# low-voltage-detector.net
KiCad netlist of a schematic drawn in EAGLE
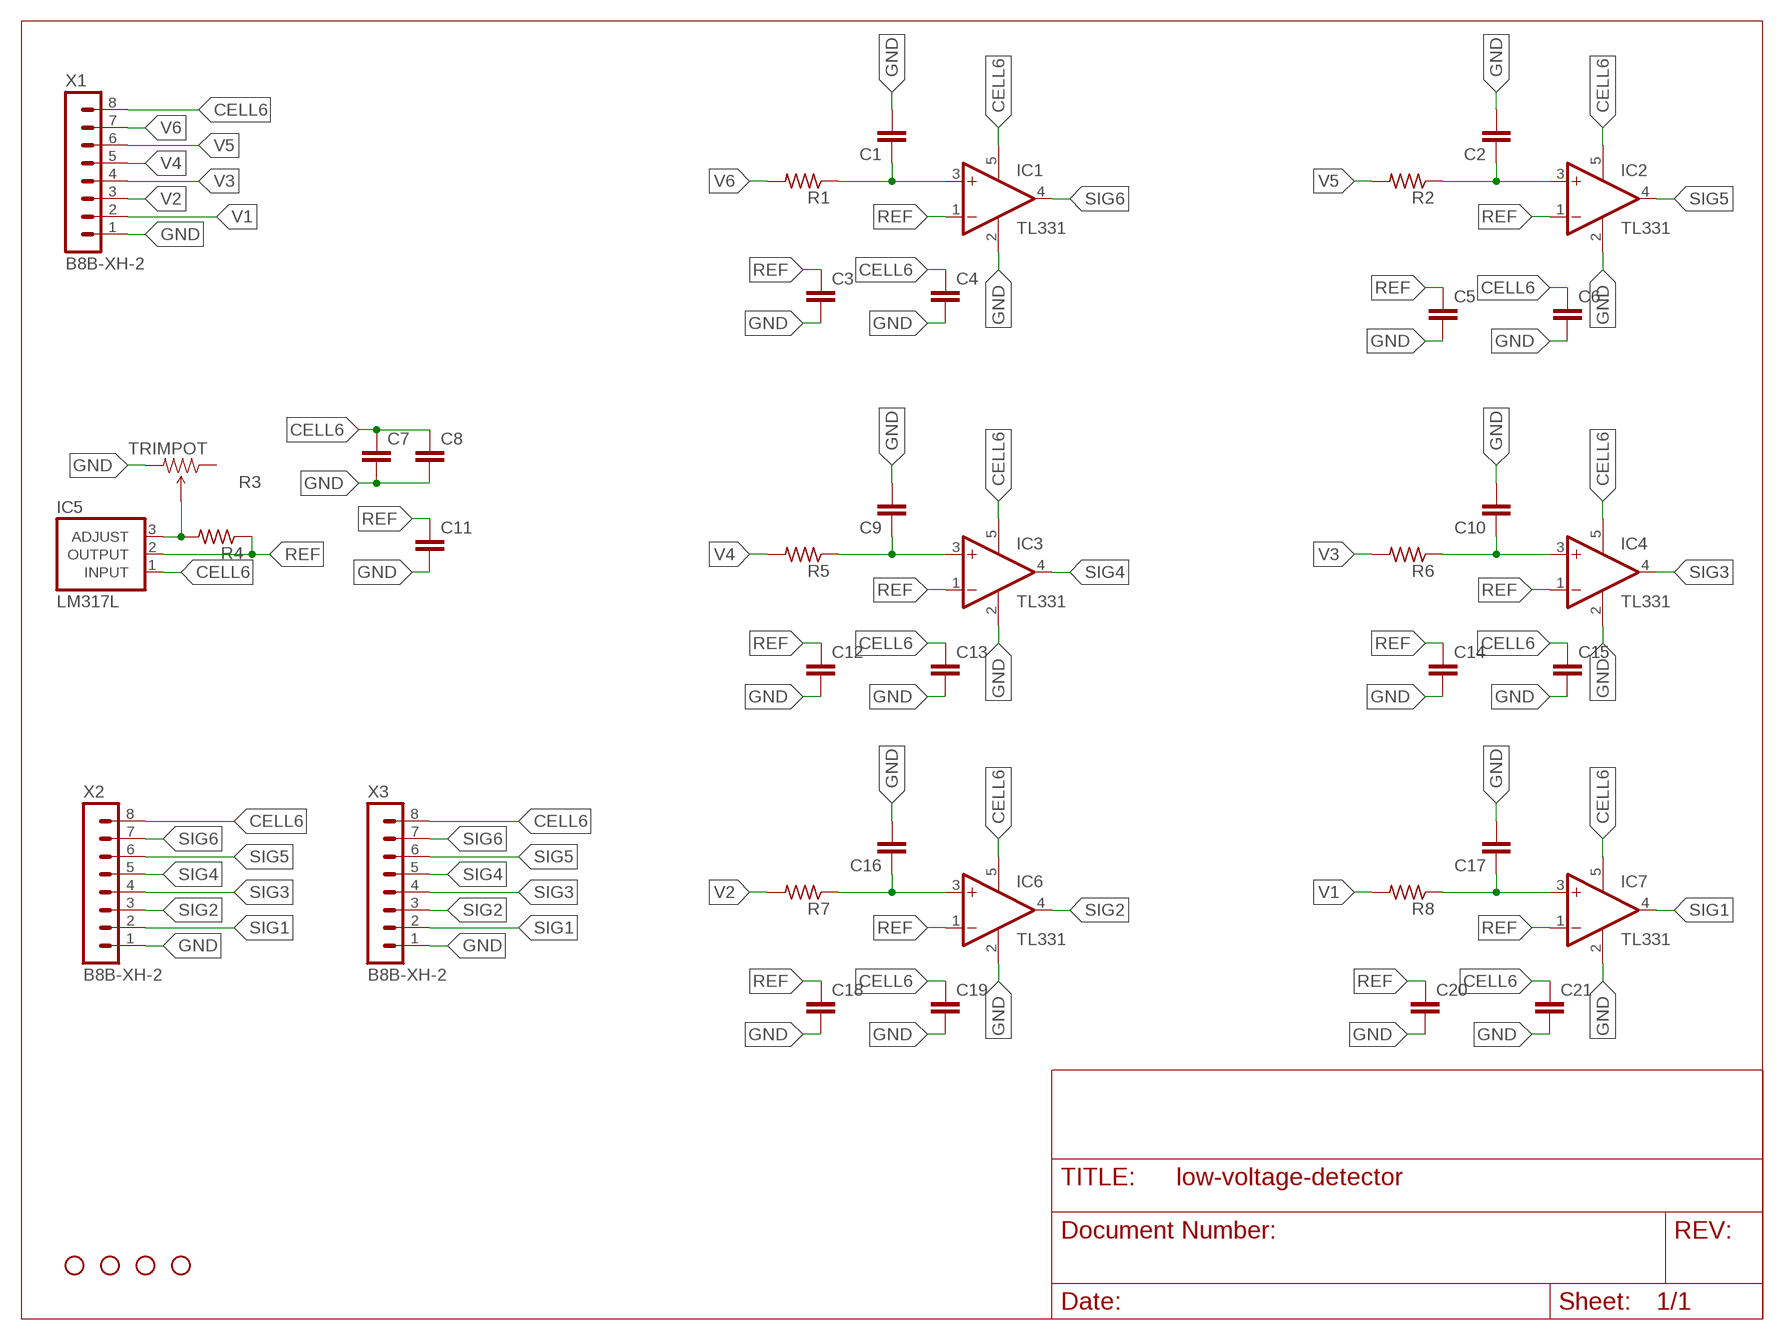
[diagram p0: schematic, sheet 1]

(export (version "E")
  (design (tool "Eeschema 10.0.6"))
  (components
    (comp (ref "C1")
      (value "CAPACITOR_0805")
      (footprint "eagle-import:0805")
      (libsource (lib "eagle-import") (part "CAPACITOR_0805"))
    )
    (comp (ref "C2")
      (value "CAPACITOR_0805")
      (footprint "eagle-import:0805")
      (libsource (lib "eagle-import") (part "CAPACITOR_0805"))
    )
    (comp (ref "C3")
      (value "CAPACITOR_0805")
      (footprint "eagle-import:0805")
      (libsource (lib "eagle-import") (part "CAPACITOR_0805"))
    )
    (comp (ref "C4")
      (value "CAPACITOR_0805")
      (footprint "eagle-import:0805")
      (libsource (lib "eagle-import") (part "CAPACITOR_0805"))
    )
    (comp (ref "C5")
      (value "CAPACITOR_0805")
      (footprint "eagle-import:0805")
      (libsource (lib "eagle-import") (part "CAPACITOR_0805"))
    )
    (comp (ref "C6")
      (value "CAPACITOR_0805")
      (footprint "eagle-import:0805")
      (libsource (lib "eagle-import") (part "CAPACITOR_0805"))
    )
    (comp (ref "C7")
      (value "CAPACITOR_0805")
      (footprint "eagle-import:0805")
      (libsource (lib "eagle-import") (part "CAPACITOR_0805"))
    )
    (comp (ref "C8")
      (value "CAPACITOR_0805")
      (footprint "eagle-import:0805")
      (libsource (lib "eagle-import") (part "CAPACITOR_0805"))
    )
    (comp (ref "C9")
      (value "CAPACITOR_0805")
      (footprint "eagle-import:0805")
      (libsource (lib "eagle-import") (part "CAPACITOR_0805"))
    )
    (comp (ref "C10")
      (value "CAPACITOR_0805")
      (footprint "eagle-import:0805")
      (libsource (lib "eagle-import") (part "CAPACITOR_0805"))
    )
    (comp (ref "C11")
      (value "CAPACITOR_0805")
      (footprint "eagle-import:0805")
      (libsource (lib "eagle-import") (part "CAPACITOR_0805"))
    )
    (comp (ref "C12")
      (value "CAPACITOR_0805")
      (footprint "eagle-import:0805")
      (libsource (lib "eagle-import") (part "CAPACITOR_0805"))
    )
    (comp (ref "C13")
      (value "CAPACITOR_0805")
      (footprint "eagle-import:0805")
      (libsource (lib "eagle-import") (part "CAPACITOR_0805"))
    )
    (comp (ref "C14")
      (value "CAPACITOR_0805")
      (footprint "eagle-import:0805")
      (libsource (lib "eagle-import") (part "CAPACITOR_0805"))
    )
    (comp (ref "C15")
      (value "CAPACITOR_0805")
      (footprint "eagle-import:0805")
      (libsource (lib "eagle-import") (part "CAPACITOR_0805"))
    )
    (comp (ref "C16")
      (value "CAPACITOR_0805")
      (footprint "eagle-import:0805")
      (libsource (lib "eagle-import") (part "CAPACITOR_0805"))
    )
    (comp (ref "C17")
      (value "CAPACITOR_0805")
      (footprint "eagle-import:0805")
      (libsource (lib "eagle-import") (part "CAPACITOR_0805"))
    )
    (comp (ref "C18")
      (value "CAPACITOR_0805")
      (footprint "eagle-import:0805")
      (libsource (lib "eagle-import") (part "CAPACITOR_0805"))
    )
    (comp (ref "C19")
      (value "CAPACITOR_0805")
      (footprint "eagle-import:0805")
      (libsource (lib "eagle-import") (part "CAPACITOR_0805"))
    )
    (comp (ref "C20")
      (value "CAPACITOR_0805")
      (footprint "eagle-import:0805")
      (libsource (lib "eagle-import") (part "CAPACITOR_0805"))
    )
    (comp (ref "C21")
      (value "CAPACITOR_0805")
      (footprint "eagle-import:0805")
      (libsource (lib "eagle-import") (part "CAPACITOR_0805"))
    )
    (comp (ref "H1")
      (value "STAND-OFF")
      (footprint "eagle-import:STAND-OFF")
      (libsource (lib "eagle-import") (part "STAND-OFF"))
    )
    (comp (ref "H2")
      (value "STAND-OFF")
      (footprint "eagle-import:STAND-OFF")
      (libsource (lib "eagle-import") (part "STAND-OFF"))
    )
    (comp (ref "H3")
      (value "STAND-OFF")
      (footprint "eagle-import:STAND-OFF")
      (libsource (lib "eagle-import") (part "STAND-OFF"))
    )
    (comp (ref "H4")
      (value "STAND-OFF")
      (footprint "eagle-import:STAND-OFF")
      (libsource (lib "eagle-import") (part "STAND-OFF"))
    )
    (comp (ref "IC1")
      (value "TL331")
      (footprint "eagle-import:DBV-R-PDSO-G5")
      (libsource (lib "eagle-import") (part "TL331"))
    )
    (comp (ref "IC2")
      (value "TL331")
      (footprint "eagle-import:DBV-R-PDSO-G5")
      (libsource (lib "eagle-import") (part "TL331"))
    )
    (comp (ref "IC3")
      (value "TL331")
      (footprint "eagle-import:DBV-R-PDSO-G5")
      (libsource (lib "eagle-import") (part "TL331"))
    )
    (comp (ref "IC4")
      (value "TL331")
      (footprint "eagle-import:DBV-R-PDSO-G5")
      (libsource (lib "eagle-import") (part "TL331"))
    )
    (comp (ref "IC5")
      (value "LM317L")
      (footprint "eagle-import:TO92")
      (libsource (lib "eagle-import") (part "LINEAR-REGULATOR_LM317L"))
    )
    (comp (ref "IC6")
      (value "TL331")
      (footprint "eagle-import:DBV-R-PDSO-G5")
      (libsource (lib "eagle-import") (part "TL331"))
    )
    (comp (ref "IC7")
      (value "TL331")
      (footprint "eagle-import:DBV-R-PDSO-G5")
      (libsource (lib "eagle-import") (part "TL331"))
    )
    (comp (ref "R1")
      (value "R-US_R0805")
      (footprint "eagle-import:R0805")
      (libsource (lib "eagle-import") (part "R-US_R0805"))
    )
    (comp (ref "R2")
      (value "R-US_R0805")
      (footprint "eagle-import:R0805")
      (libsource (lib "eagle-import") (part "R-US_R0805"))
    )
    (comp (ref "R3")
      (value "TRIMPOT")
      (footprint "eagle-import:490-2877-ND")
      (libsource (lib "eagle-import") (part "TRIMPOT"))
    )
    (comp (ref "R4")
      (value "R-US_R0805")
      (footprint "eagle-import:R0805")
      (libsource (lib "eagle-import") (part "R-US_R0805"))
    )
    (comp (ref "R5")
      (value "R-US_R0805")
      (footprint "eagle-import:R0805")
      (libsource (lib "eagle-import") (part "R-US_R0805"))
    )
    (comp (ref "R6")
      (value "R-US_R0805")
      (footprint "eagle-import:R0805")
      (libsource (lib "eagle-import") (part "R-US_R0805"))
    )
    (comp (ref "R7")
      (value "R-US_R0805")
      (footprint "eagle-import:R0805")
      (libsource (lib "eagle-import") (part "R-US_R0805"))
    )
    (comp (ref "R8")
      (value "R-US_R0805")
      (footprint "eagle-import:R0805")
      (libsource (lib "eagle-import") (part "R-US_R0805"))
    )
    (comp (ref "X1")
      (value "B8B-XH-2")
      (footprint "eagle-import:B8B-XH-A")
      (libsource (lib "eagle-import") (part "B8B-XH-2"))
    )
    (comp (ref "X2")
      (value "B8B-XH-2")
      (footprint "eagle-import:B8B-XH-A")
      (libsource (lib "eagle-import") (part "B8B-XH-2"))
    )
    (comp (ref "X3")
      (value "B8B-XH-2")
      (footprint "eagle-import:B8B-XH-A")
      (libsource (lib "eagle-import") (part "B8B-XH-2"))
    )
  )
  (nets
    (net (code "1") (name "CELL6") (class "Default")
      (node (ref "C13") (pin "1") (pinfunction "1_1") (pintype "passive"))
      (node (ref "C15") (pin "1") (pinfunction "1_1") (pintype "passive"))
      (node (ref "C19") (pin "1") (pinfunction "1_1") (pintype "passive"))
      (node (ref "C21") (pin "1") (pinfunction "1_1") (pintype "passive"))
      (node (ref "C4") (pin "1") (pinfunction "1_1") (pintype "passive"))
      (node (ref "C6") (pin "1") (pinfunction "1_1") (pintype "passive"))
      (node (ref "C7") (pin "1") (pinfunction "1_1") (pintype "passive"))
      (node (ref "C8") (pin "1") (pinfunction "1_1") (pintype "passive"))
      (node (ref "IC1") (pin "5") (pinfunction "V+_5") (pintype "power_in"))
      (node (ref "IC2") (pin "5") (pinfunction "V+_5") (pintype "power_in"))
      (node (ref "IC3") (pin "5") (pinfunction "V+_5") (pintype "power_in"))
      (node (ref "IC4") (pin "5") (pinfunction "V+_5") (pintype "power_in"))
      (node (ref "IC5") (pin "1") (pinfunction "INPUT_1") (pintype "bidirectional"))
      (node (ref "IC6") (pin "5") (pinfunction "V+_5") (pintype "power_in"))
      (node (ref "IC7") (pin "5") (pinfunction "V+_5") (pintype "power_in"))
      (node (ref "X1") (pin "8") (pinfunction "8_8") (pintype "passive"))
      (node (ref "X2") (pin "8") (pinfunction "8_8") (pintype "passive"))
      (node (ref "X3") (pin "8") (pinfunction "8_8") (pintype "passive"))
    )
    (net (code "2") (name "GND") (class "Default")
      (node (ref "C1") (pin "2") (pinfunction "2_2") (pintype "passive"))
      (node (ref "C10") (pin "2") (pinfunction "2_2") (pintype "passive"))
      (node (ref "C11") (pin "2") (pinfunction "2_2") (pintype "passive"))
      (node (ref "C12") (pin "2") (pinfunction "2_2") (pintype "passive"))
      (node (ref "C13") (pin "2") (pinfunction "2_2") (pintype "passive"))
      (node (ref "C14") (pin "2") (pinfunction "2_2") (pintype "passive"))
      (node (ref "C15") (pin "2") (pinfunction "2_2") (pintype "passive"))
      (node (ref "C16") (pin "2") (pinfunction "2_2") (pintype "passive"))
      (node (ref "C17") (pin "2") (pinfunction "2_2") (pintype "passive"))
      (node (ref "C18") (pin "2") (pinfunction "2_2") (pintype "passive"))
      (node (ref "C19") (pin "2") (pinfunction "2_2") (pintype "passive"))
      (node (ref "C2") (pin "2") (pinfunction "2_2") (pintype "passive"))
      (node (ref "C20") (pin "2") (pinfunction "2_2") (pintype "passive"))
      (node (ref "C21") (pin "2") (pinfunction "2_2") (pintype "passive"))
      (node (ref "C3") (pin "2") (pinfunction "2_2") (pintype "passive"))
      (node (ref "C4") (pin "2") (pinfunction "2_2") (pintype "passive"))
      (node (ref "C5") (pin "2") (pinfunction "2_2") (pintype "passive"))
      (node (ref "C6") (pin "2") (pinfunction "2_2") (pintype "passive"))
      (node (ref "C7") (pin "2") (pinfunction "2_2") (pintype "passive"))
      (node (ref "C8") (pin "2") (pinfunction "2_2") (pintype "passive"))
      (node (ref "C9") (pin "2") (pinfunction "2_2") (pintype "passive"))
      (node (ref "IC1") (pin "2") (pinfunction "GND_2") (pintype "power_in"))
      (node (ref "IC2") (pin "2") (pinfunction "GND_2") (pintype "power_in"))
      (node (ref "IC3") (pin "2") (pinfunction "GND_2") (pintype "power_in"))
      (node (ref "IC4") (pin "2") (pinfunction "GND_2") (pintype "power_in"))
      (node (ref "IC6") (pin "2") (pinfunction "GND_2") (pintype "power_in"))
      (node (ref "IC7") (pin "2") (pinfunction "GND_2") (pintype "power_in"))
      (node (ref "R3") (pin "P$3") (pinfunction "CW_P$3") (pintype "passive"))
      (node (ref "X1") (pin "1") (pinfunction "1_1") (pintype "passive"))
      (node (ref "X2") (pin "1") (pinfunction "1_1") (pintype "passive"))
      (node (ref "X3") (pin "1") (pinfunction "1_1") (pintype "passive"))
    )
    (net (code "3") (name "Net-(IC1-+IN)") (class "Default")
      (node (ref "C1") (pin "1") (pinfunction "1_1") (pintype "passive"))
      (node (ref "IC1") (pin "3") (pinfunction "+IN_3") (pintype "input"))
      (node (ref "R1") (pin "1") (pinfunction "1_1") (pintype "passive"))
    )
    (net (code "4") (name "Net-(IC2-+IN)") (class "Default")
      (node (ref "C2") (pin "1") (pinfunction "1_1") (pintype "passive"))
      (node (ref "IC2") (pin "3") (pinfunction "+IN_3") (pintype "input"))
      (node (ref "R2") (pin "1") (pinfunction "1_1") (pintype "passive"))
    )
    (net (code "5") (name "Net-(IC3-+IN)") (class "Default")
      (node (ref "C9") (pin "1") (pinfunction "1_1") (pintype "passive"))
      (node (ref "IC3") (pin "3") (pinfunction "+IN_3") (pintype "input"))
      (node (ref "R5") (pin "1") (pinfunction "1_1") (pintype "passive"))
    )
    (net (code "6") (name "Net-(IC4-+IN)") (class "Default")
      (node (ref "C10") (pin "1") (pinfunction "1_1") (pintype "passive"))
      (node (ref "IC4") (pin "3") (pinfunction "+IN_3") (pintype "input"))
      (node (ref "R6") (pin "1") (pinfunction "1_1") (pintype "passive"))
    )
    (net (code "7") (name "Net-(IC5-ADJUST)") (class "Default")
      (node (ref "IC5") (pin "3") (pinfunction "ADJUST_3") (pintype "bidirectional"))
      (node (ref "R3") (pin "P$2") (pinfunction "WIPER_P$2") (pintype "passive"))
      (node (ref "R4") (pin "2") (pinfunction "2_2") (pintype "passive"))
    )
    (net (code "8") (name "Net-(IC6-+IN)") (class "Default")
      (node (ref "C16") (pin "1") (pinfunction "1_1") (pintype "passive"))
      (node (ref "IC6") (pin "3") (pinfunction "+IN_3") (pintype "input"))
      (node (ref "R7") (pin "1") (pinfunction "1_1") (pintype "passive"))
    )
    (net (code "9") (name "Net-(IC7-+IN)") (class "Default")
      (node (ref "C17") (pin "1") (pinfunction "1_1") (pintype "passive"))
      (node (ref "IC7") (pin "3") (pinfunction "+IN_3") (pintype "input"))
      (node (ref "R8") (pin "1") (pinfunction "1_1") (pintype "passive"))
    )
    (net (code "10") (name "REF") (class "Default")
      (node (ref "C11") (pin "1") (pinfunction "1_1") (pintype "passive"))
      (node (ref "C12") (pin "1") (pinfunction "1_1") (pintype "passive"))
      (node (ref "C14") (pin "1") (pinfunction "1_1") (pintype "passive"))
      (node (ref "C18") (pin "1") (pinfunction "1_1") (pintype "passive"))
      (node (ref "C20") (pin "1") (pinfunction "1_1") (pintype "passive"))
      (node (ref "C3") (pin "1") (pinfunction "1_1") (pintype "passive"))
      (node (ref "C5") (pin "1") (pinfunction "1_1") (pintype "passive"))
      (node (ref "IC1") (pin "1") (pinfunction "-IN_1") (pintype "input"))
      (node (ref "IC2") (pin "1") (pinfunction "-IN_1") (pintype "input"))
      (node (ref "IC3") (pin "1") (pinfunction "-IN_1") (pintype "input"))
      (node (ref "IC4") (pin "1") (pinfunction "-IN_1") (pintype "input"))
      (node (ref "IC5") (pin "2") (pinfunction "OUTPUT_2") (pintype "bidirectional"))
      (node (ref "IC6") (pin "1") (pinfunction "-IN_1") (pintype "input"))
      (node (ref "IC7") (pin "1") (pinfunction "-IN_1") (pintype "input"))
      (node (ref "R4") (pin "1") (pinfunction "1_1") (pintype "passive"))
    )
    (net (code "11") (name "SIG1") (class "Default")
      (node (ref "IC7") (pin "4") (pinfunction "OUT_4") (pintype "output"))
      (node (ref "X2") (pin "2") (pinfunction "2_2") (pintype "passive"))
      (node (ref "X3") (pin "2") (pinfunction "2_2") (pintype "passive"))
    )
    (net (code "12") (name "SIG2") (class "Default")
      (node (ref "IC6") (pin "4") (pinfunction "OUT_4") (pintype "output"))
      (node (ref "X2") (pin "3") (pinfunction "3_3") (pintype "passive"))
      (node (ref "X3") (pin "3") (pinfunction "3_3") (pintype "passive"))
    )
    (net (code "13") (name "SIG3") (class "Default")
      (node (ref "IC4") (pin "4") (pinfunction "OUT_4") (pintype "output"))
      (node (ref "X2") (pin "4") (pinfunction "4_4") (pintype "passive"))
      (node (ref "X3") (pin "4") (pinfunction "4_4") (pintype "passive"))
    )
    (net (code "14") (name "SIG4") (class "Default")
      (node (ref "IC3") (pin "4") (pinfunction "OUT_4") (pintype "output"))
      (node (ref "X2") (pin "5") (pinfunction "5_5") (pintype "passive"))
      (node (ref "X3") (pin "5") (pinfunction "5_5") (pintype "passive"))
    )
    (net (code "15") (name "SIG5") (class "Default")
      (node (ref "IC2") (pin "4") (pinfunction "OUT_4") (pintype "output"))
      (node (ref "X2") (pin "6") (pinfunction "6_6") (pintype "passive"))
      (node (ref "X3") (pin "6") (pinfunction "6_6") (pintype "passive"))
    )
    (net (code "16") (name "SIG6") (class "Default")
      (node (ref "IC1") (pin "4") (pinfunction "OUT_4") (pintype "output"))
      (node (ref "X2") (pin "7") (pinfunction "7_7") (pintype "passive"))
      (node (ref "X3") (pin "7") (pinfunction "7_7") (pintype "passive"))
    )
    (net (code "17") (name "V1") (class "Default")
      (node (ref "R8") (pin "2") (pinfunction "2_2") (pintype "passive"))
      (node (ref "X1") (pin "2") (pinfunction "2_2") (pintype "passive"))
    )
    (net (code "18") (name "V2") (class "Default")
      (node (ref "R7") (pin "2") (pinfunction "2_2") (pintype "passive"))
      (node (ref "X1") (pin "3") (pinfunction "3_3") (pintype "passive"))
    )
    (net (code "19") (name "V3") (class "Default")
      (node (ref "R6") (pin "2") (pinfunction "2_2") (pintype "passive"))
      (node (ref "X1") (pin "4") (pinfunction "4_4") (pintype "passive"))
    )
    (net (code "20") (name "V4") (class "Default")
      (node (ref "R5") (pin "2") (pinfunction "2_2") (pintype "passive"))
      (node (ref "X1") (pin "5") (pinfunction "5_5") (pintype "passive"))
    )
    (net (code "21") (name "V5") (class "Default")
      (node (ref "R2") (pin "2") (pinfunction "2_2") (pintype "passive"))
      (node (ref "X1") (pin "6") (pinfunction "6_6") (pintype "passive"))
    )
    (net (code "22") (name "V6") (class "Default")
      (node (ref "R1") (pin "2") (pinfunction "2_2") (pintype "passive"))
      (node (ref "X1") (pin "7") (pinfunction "7_7") (pintype "passive"))
    )
    (net (code "23") (name "unconnected-(R3-CCW-PadP$1)") (class "Default")
      (node (ref "R3") (pin "P$1") (pinfunction "CCW_P$1") (pintype "passive"))
    )
  )
)
